# p2b-001.net
KiCad netlist of a schematic drawn in EAGLE
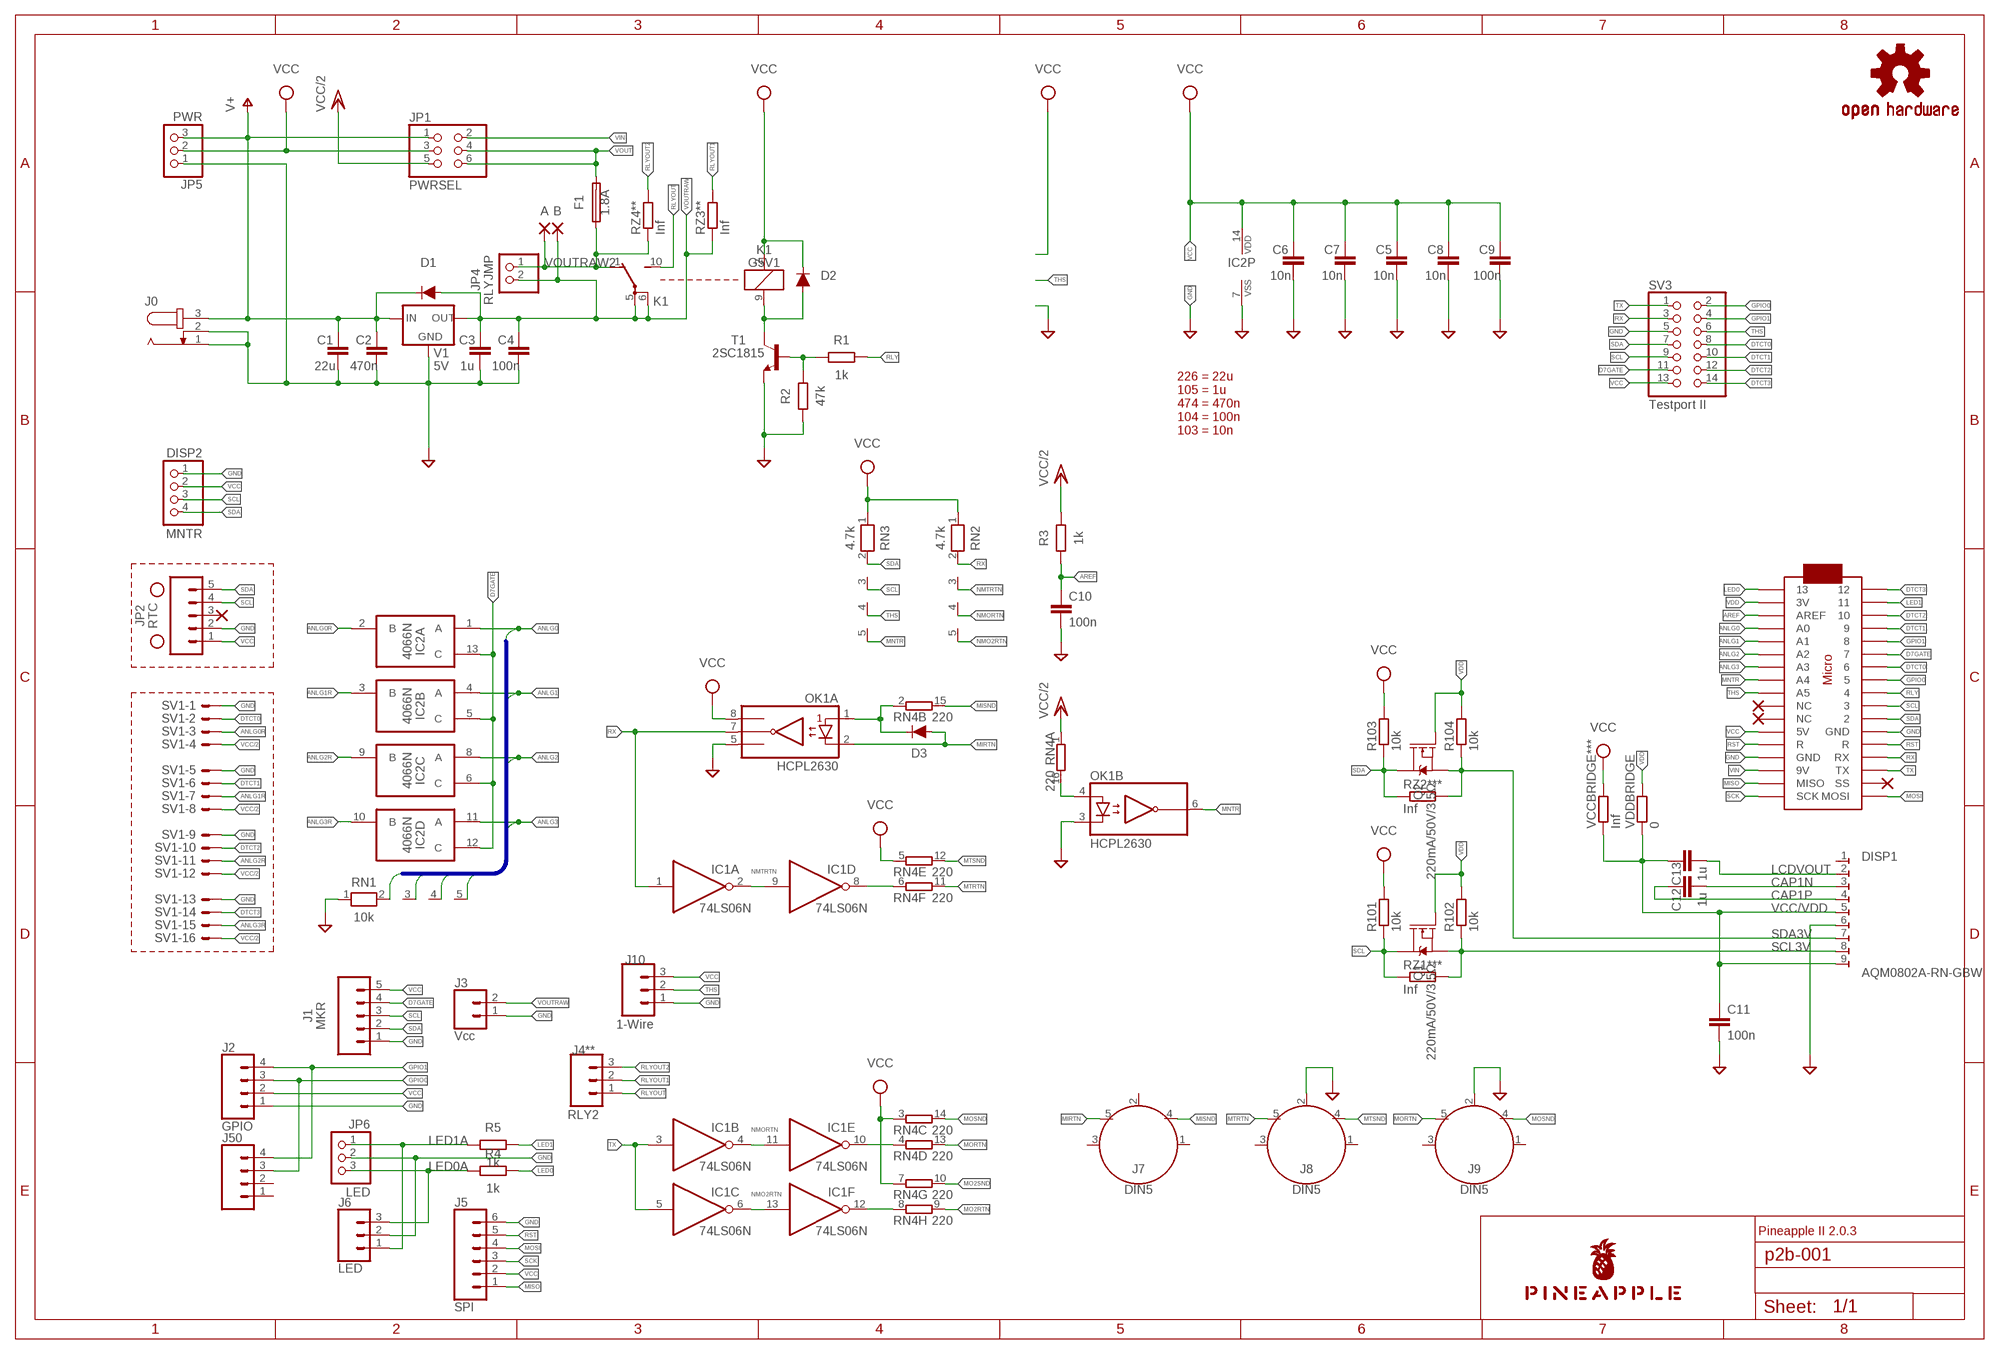
[diagram p0: schematic, sheet 1]

(export (version "E")
  (design (tool "Eeschema 10.0.6"))
  (components
    (comp (ref "A")
      (value "SMD2")
      (footprint "eagle-import:SMD1,27-2,54")
      (libsource (lib "eagle-import") (part "SMD2"))
    )
    (comp (ref "B")
      (value "SMD2")
      (footprint "eagle-import:SMD1,27-2,54")
      (libsource (lib "eagle-import") (part "SMD2"))
    )
    (comp (ref "C1")
      (value "22u")
      (footprint "eagle-import:C025-050X050")
      (libsource (lib "eagle-import") (part "C-EU025-050X050"))
    )
    (comp (ref "C2")
      (value "470n")
      (footprint "eagle-import:C050-024X044")
      (libsource (lib "eagle-import") (part "C-EU050-024X044"))
    )
    (comp (ref "C3")
      (value "1u")
      (footprint "eagle-import:C050-024X044")
      (libsource (lib "eagle-import") (part "C-EU050-024X044"))
    )
    (comp (ref "C4")
      (value "100n")
      (footprint "eagle-import:C025-024X044")
      (libsource (lib "eagle-import") (part "C-EU025-024X044"))
    )
    (comp (ref "C5")
      (value "10n")
      (footprint "eagle-import:C025-024X044")
      (libsource (lib "eagle-import") (part "resistor_348_C-EU025-024X044"))
    )
    (comp (ref "C6")
      (value "10n")
      (footprint "eagle-import:C025-024X044")
      (libsource (lib "eagle-import") (part "resistor_348_C-EU025-024X044"))
    )
    (comp (ref "C7")
      (value "10n")
      (footprint "eagle-import:C025-024X044")
      (libsource (lib "eagle-import") (part "resistor_348_C-EU025-024X044"))
    )
    (comp (ref "C8")
      (value "10n")
      (footprint "eagle-import:C025-024X044")
      (libsource (lib "eagle-import") (part "resistor_348_C-EU025-024X044"))
    )
    (comp (ref "C9")
      (value "100n")
      (footprint "eagle-import:C025-024X044")
      (libsource (lib "eagle-import") (part "resistor_348_C-EU025-024X044"))
    )
    (comp (ref "C10")
      (value "100n")
      (footprint "eagle-import:C025-024X044")
      (libsource (lib "eagle-import") (part "C-EU025-024X044"))
    )
    (comp (ref "C11")
      (value "100n")
      (footprint "eagle-import:C025-024X044")
      (libsource (lib "eagle-import") (part "C-EU025-024X044"))
    )
    (comp (ref "C12")
      (value "1u")
      (footprint "eagle-import:C050-024X044")
      (libsource (lib "eagle-import") (part "C-EU050-024X044"))
    )
    (comp (ref "C13")
      (value "1u")
      (footprint "eagle-import:C050-024X044")
      (libsource (lib "eagle-import") (part "C-EU050-024X044"))
    )
    (comp (ref "D1")
      (value "DIODE-1N4148")
      (footprint "eagle-import:DIODE-1N4148")
      (libsource (lib "eagle-import") (part "DIODE-1N4148"))
    )
    (comp (ref "D2")
      (value "DIODE-1N4148")
      (footprint "eagle-import:DIODE-1N4148")
      (libsource (lib "eagle-import") (part "DIODE-1N4148"))
    )
    (comp (ref "D3")
      (value "DIODE-1N4148")
      (footprint "eagle-import:DIODE-1N4148")
      (libsource (lib "eagle-import") (part "DIODE-1N4148"))
    )
    (comp (ref "DISP1")
      (value "AQM0802A-RN-GBW")
      (footprint "eagle-import:AQM0802A-RN-GBW-FOOTPRINT")
      (libsource (lib "eagle-import") (part "AQM0802A-RN-GBW"))
    )
    (comp (ref "DISP2")
      (value "MNTR")
      (footprint "eagle-import:1X04")
      (libsource (lib "eagle-import") (part "PINHD-1X4"))
    )
    (comp (ref "F1")
      (value "1.8A")
      (footprint "eagle-import:TE5")
      (libsource (lib "eagle-import") (part "TE5"))
    )
    (comp (ref "H1")
      (value "STAND-OFF")
      (footprint "eagle-import:STAND-OFF")
      (libsource (lib "eagle-import") (part "STAND-OFF"))
    )
    (comp (ref "H2")
      (value "STAND-OFF")
      (footprint "eagle-import:STAND-OFF")
      (libsource (lib "eagle-import") (part "STAND-OFF"))
    )
    (comp (ref "IC1")
      (value "74LS06N")
      (footprint "eagle-import:DIL14")
      (libsource (lib "eagle-import") (part "7406NLS"))
    )
    (comp (ref "IC2")
      (value "4066N")
      (footprint "eagle-import:DIL14")
      (libsource (lib "eagle-import") (part "4066N"))
    )
    (comp (ref "J0")
      (value "JACK-PLUG0")
      (footprint "eagle-import:SPC4077")
      (libsource (lib "eagle-import") (part "JACK-PLUG0"))
    )
    (comp (ref "J1")
      (value "MKR")
      (footprint "eagle-import:JST-5-PTH")
      (libsource (lib "eagle-import") (part "CONN_05JST"))
    )
    (comp (ref "J2")
      (value "GPIO")
      (footprint "eagle-import:JST-4-PTH")
      (libsource (lib "eagle-import") (part "CONN_04JST-PTH"))
    )
    (comp (ref "J3")
      (value "Vcc")
      (footprint "eagle-import:JST-2-PTH")
      (libsource (lib "eagle-import") (part "CONN_02JST-PTH-2"))
    )
    (comp (ref "J4**")
      (value "RLY2")
      (footprint "eagle-import:JST-3-PTH-NS")
      (libsource (lib "eagle-import") (part "CONN_03JST-PTH-NS"))
    )
    (comp (ref "J5")
      (value "SPI")
      (footprint "eagle-import:1X06_1.27MM")
      (libsource (lib "eagle-import") (part "CONN_061.27MM"))
    )
    (comp (ref "J6")
      (value "LED")
      (footprint "eagle-import:JST-3-PTH-VERT")
      (libsource (lib "eagle-import") (part "CONN_03JST-PTH-VERT"))
    )
    (comp (ref "J7")
      (value "DIN5")
      (footprint "eagle-import:DIN5-RA-PTH")
      (libsource (lib "eagle-import") (part "DIN5"))
    )
    (comp (ref "J8")
      (value "DIN5")
      (footprint "eagle-import:DIN5-RA-PTH")
      (libsource (lib "eagle-import") (part "DIN5"))
    )
    (comp (ref "J9")
      (value "DIN5")
      (footprint "eagle-import:DIN5-RA-PTH")
      (libsource (lib "eagle-import") (part "DIN5"))
    )
    (comp (ref "J10")
      (value "1-Wire")
      (footprint "eagle-import:JST-3-PTH-VERT")
      (libsource (lib "eagle-import") (part "CONN_03JST-PTH-VERT"))
    )
    (comp (ref "J50")
      (value "CONN_041.27MM")
      (footprint "eagle-import:1X04_1.27MM")
      (libsource (lib "eagle-import") (part "CONN_041.27MM"))
    )
    (comp (ref "JP1")
      (value "PWRSEL")
      (footprint "eagle-import:2X03")
      (libsource (lib "eagle-import") (part "PINHD-2X3"))
    )
    (comp (ref "JP2")
      (value "RTC")
      (footprint "eagle-import:1X05")
      (libsource (lib "eagle-import") (part "CONN_05"))
    )
    (comp (ref "JP4")
      (value "RLYJMP")
      (footprint "eagle-import:1X02")
      (libsource (lib "eagle-import") (part "PINHD-1X2"))
    )
    (comp (ref "JP5")
      (value "PWR")
      (footprint "eagle-import:1X03")
      (libsource (lib "eagle-import") (part "PINHD-1X3"))
    )
    (comp (ref "JP6")
      (value "LED")
      (footprint "eagle-import:1X03")
      (libsource (lib "eagle-import") (part "PINHD-1X3"))
    )
    (comp (ref "K1")
      (value "G5V1")
      (footprint "eagle-import:G5V1")
      (fields (field (name "MPN") "G5V-1-DC24"))
      (libsource (lib "eagle-import") (part "G5V1"))
    )
    (comp (ref "LOGO1")
      (value "OSHW-LOGOS-COPPER")
      (footprint "eagle-import:OSHW-LOGO-S_COPPER")
      (libsource (lib "eagle-import") (part "OSHW-LOGOS-COPPER"))
    )
    (comp (ref "MC1")
      (value "ARDUINOMICRO")
      (footprint "eagle-import:ARDUINOMICRO")
      (libsource (lib "eagle-import") (part "ARDUINOMICRO"))
    )
    (comp (ref "OK1")
      (value "HCPL2630")
      (footprint "eagle-import:DIL08")
      (fields (field (name "MF") "AGILENT TECHNOLOGIES") (field (name "MPN") "HCPL-2630-000E"))
      (libsource (lib "eagle-import") (part "HCPL2630"))
    )
    (comp (ref "Q1")
      (value "220mA/50V/3.5Ω")
      (footprint "eagle-import:SOT23-3")
      (libsource (lib "eagle-import") (part "MOSFET-NCH-BSS138"))
    )
    (comp (ref "Q2")
      (value "220mA/50V/3.5Ω")
      (footprint "eagle-import:SOT23-3")
      (libsource (lib "eagle-import") (part "MOSFET-NCH-BSS138"))
    )
    (comp (ref "R1")
      (value "1k")
      (footprint "eagle-import:0204_5")
      (libsource (lib "eagle-import") (part "resistor_348_R-EU_0204/5"))
    )
    (comp (ref "R2")
      (value "47k")
      (footprint "eagle-import:0204_5")
      (libsource (lib "eagle-import") (part "resistor_348_R-EU_0204/5"))
    )
    (comp (ref "R3")
      (value "1k")
      (footprint "eagle-import:0204_5")
      (libsource (lib "eagle-import") (part "resistor_348_R-EU_0204/5"))
    )
    (comp (ref "R4")
      (value "1k")
      (footprint "eagle-import:0204_5")
      (libsource (lib "eagle-import") (part "resistor_348_R-EU_0204/5"))
    )
    (comp (ref "R5")
      (value "1k")
      (footprint "eagle-import:0204_5")
      (libsource (lib "eagle-import") (part "resistor_348_R-EU_0204/5"))
    )
    (comp (ref "R101")
      (value "10k")
      (footprint "eagle-import:M2012")
      (libsource (lib "eagle-import") (part "R-EU_M2012"))
    )
    (comp (ref "R102")
      (value "10k")
      (footprint "eagle-import:M2012")
      (libsource (lib "eagle-import") (part "R-EU_M2012"))
    )
    (comp (ref "R103")
      (value "10k")
      (footprint "eagle-import:M2012")
      (libsource (lib "eagle-import") (part "R-EU_M2012"))
    )
    (comp (ref "R104")
      (value "10k")
      (footprint "eagle-import:M2012")
      (libsource (lib "eagle-import") (part "R-EU_M2012"))
    )
    (comp (ref "RN1")
      (value "10k")
      (footprint "eagle-import:RN-5")
      (libsource (lib "eagle-import") (part "RN04"))
    )
    (comp (ref "RN2")
      (value "4.7k")
      (footprint "eagle-import:RN-5")
      (libsource (lib "eagle-import") (part "RN04"))
    )
    (comp (ref "RN3")
      (value "4.7k")
      (footprint "eagle-import:RN-5")
      (libsource (lib "eagle-import") (part "RN04"))
    )
    (comp (ref "RN4")
      (value "220")
      (footprint "eagle-import:DIL16")
      (libsource (lib "eagle-import") (part "8R-N"))
    )
    (comp (ref "RZ1***")
      (value "Inf")
      (footprint "eagle-import:M2012")
      (libsource (lib "eagle-import") (part "R-EU_M2012"))
    )
    (comp (ref "RZ2***")
      (value "Inf")
      (footprint "eagle-import:M2012")
      (libsource (lib "eagle-import") (part "R-EU_M2012"))
    )
    (comp (ref "RZ3**")
      (value "Inf")
      (footprint "eagle-import:M2012")
      (libsource (lib "eagle-import") (part "R-EU_M2012"))
    )
    (comp (ref "RZ4**")
      (value "Inf")
      (footprint "eagle-import:M2012")
      (libsource (lib "eagle-import") (part "R-EU_M2012"))
    )
    (comp (ref "SV1")
      (value "ML16LE")
      (footprint "eagle-import:ML16L")
      (libsource (lib "eagle-import") (part "ML16LE"))
    )
    (comp (ref "SV3")
      (value "Testport II")
      (footprint "eagle-import:2X07")
      (libsource (lib "eagle-import") (part "PINHD-2X7"))
    )
    (comp (ref "T1")
      (value "2SC1815")
      (footprint "eagle-import:TO92-ECB")
      (libsource (lib "eagle-import") (part "2SC1815"))
    )
    (comp (ref "U$1")
      (value "PINEAPPLE450_SILK")
      (footprint "eagle-import:PINEAPPLE450_SILK")
      (libsource (lib "eagle-import") (part "PINEAPPLE450_SILK"))
    )
    (comp (ref "V1")
      (value "5V")
      (footprint "eagle-import:78XXL")
      (libsource (lib "eagle-import") (part "78XXL"))
    )
    (comp (ref "VCCBRIDGE***")
      (value "Inf")
      (footprint "eagle-import:M2012")
      (libsource (lib "eagle-import") (part "R-EU_M2012"))
    )
    (comp (ref "VDDBRIDGE")
      (value "0")
      (footprint "eagle-import:M2012")
      (libsource (lib "eagle-import") (part "R-EU_M2012"))
    )
  )
  (nets
    (net (code "1") (name "/CAP1N") (class "Default")
      (node (ref "C12") (pin "2") (pinfunction "2_2") (pintype "passive"))
      (node (ref "DISP1") (pin "3") (pinfunction "3_3") (pintype "passive"))
    )
    (net (code "2") (name "/CAP1P") (class "Default")
      (node (ref "C12") (pin "1") (pinfunction "1_1") (pintype "passive"))
      (node (ref "DISP1") (pin "4") (pinfunction "4_4") (pintype "passive"))
    )
    (net (code "3") (name "/LCDVOUT") (class "Default")
      (node (ref "C13") (pin "2") (pinfunction "2_2") (pintype "passive"))
      (node (ref "DISP1") (pin "2") (pinfunction "2_2") (pintype "passive"))
    )
    (net (code "4") (name "/LED0A") (class "Default")
      (node (ref "J6") (pin "3") (pinfunction "3_3") (pintype "passive"))
      (node (ref "JP6") (pin "3") (pinfunction "3_3") (pintype "passive"))
      (node (ref "R4") (pin "1") (pinfunction "1_1") (pintype "passive"))
    )
    (net (code "5") (name "/LED1A") (class "Default")
      (node (ref "J6") (pin "1") (pinfunction "1_1") (pintype "passive"))
      (node (ref "JP6") (pin "1") (pinfunction "1_1") (pintype "passive"))
      (node (ref "R5") (pin "1") (pinfunction "1_1") (pintype "passive"))
    )
    (net (code "6") (name "/SCL3V") (class "Default")
      (node (ref "DISP1") (pin "8") (pinfunction "8_8") (pintype "passive"))
      (node (ref "Q1") (pin "2") (pinfunction "S_2") (pintype "bidirectional"))
      (node (ref "R102") (pin "1") (pinfunction "1_1") (pintype "passive"))
      (node (ref "RZ1***") (pin "2") (pinfunction "2_2") (pintype "passive"))
    )
    (net (code "7") (name "/SDA3V") (class "Default")
      (node (ref "DISP1") (pin "7") (pinfunction "7_7") (pintype "passive"))
      (node (ref "Q2") (pin "2") (pinfunction "S_2") (pintype "bidirectional"))
      (node (ref "R104") (pin "1") (pinfunction "1_1") (pintype "passive"))
      (node (ref "RZ2***") (pin "2") (pinfunction "2_2") (pintype "passive"))
    )
    (net (code "8") (name "/VCC{slash}VDD") (class "Default")
      (node (ref "C11") (pin "1") (pinfunction "1_1") (pintype "passive"))
      (node (ref "C13") (pin "1") (pinfunction "1_1") (pintype "passive"))
      (node (ref "DISP1") (pin "5") (pinfunction "5_5") (pintype "passive"))
      (node (ref "DISP1") (pin "9") (pinfunction "9_9") (pintype "passive"))
      (node (ref "VCCBRIDGE***") (pin "1") (pinfunction "1_1") (pintype "passive"))
      (node (ref "VDDBRIDGE") (pin "1") (pinfunction "1_1") (pintype "passive"))
    )
    (net (code "9") (name "/VOUTRAW2") (class "Default")
      (node (ref "A") (pin "1") (pinfunction "P_1") (pintype "passive"))
      (node (ref "F1") (pin "1") (pinfunction "1_1") (pintype "passive"))
      (node (ref "JP4") (pin "1") (pinfunction "1_1") (pintype "passive"))
      (node (ref "K1") (pin "1") (pinfunction "O_1") (pintype "passive"))
      (node (ref "RZ4**") (pin "1") (pinfunction "1_1") (pintype "passive"))
    )
    (net (code "10") (name "ANLG0") (class "Default")
      (node (ref "IC2") (pin "1") (pinfunction "A_1") (pintype "tri_state"))
      (node (ref "MC1") (pin "P$31") (pinfunction "A0_P$31") (pintype "bidirectional"))
      (node (ref "RN1") (pin "2") (pinfunction "2_2") (pintype "passive"))
    )
    (net (code "11") (name "ANLG0R") (class "Default")
      (node (ref "IC2") (pin "2") (pinfunction "B_2") (pintype "tri_state"))
      (node (ref "SV1") (pin "3") (pinfunction "S_3") (pintype "passive"))
    )
    (net (code "12") (name "ANLG1") (class "Default")
      (node (ref "IC2") (pin "4") (pinfunction "A_4") (pintype "tri_state"))
      (node (ref "MC1") (pin "P$30") (pinfunction "A1_P$30") (pintype "bidirectional"))
      (node (ref "RN1") (pin "3") (pinfunction "3_3") (pintype "passive"))
    )
    (net (code "13") (name "ANLG1R") (class "Default")
      (node (ref "IC2") (pin "3") (pinfunction "B_3") (pintype "tri_state"))
      (node (ref "SV1") (pin "7") (pinfunction "S_7") (pintype "passive"))
    )
    (net (code "14") (name "ANLG2") (class "Default")
      (node (ref "IC2") (pin "8") (pinfunction "A_8") (pintype "tri_state"))
      (node (ref "MC1") (pin "P$29") (pinfunction "A2_P$29") (pintype "bidirectional"))
      (node (ref "RN1") (pin "4") (pinfunction "4_4") (pintype "passive"))
    )
    (net (code "15") (name "ANLG2R") (class "Default")
      (node (ref "IC2") (pin "9") (pinfunction "B_9") (pintype "tri_state"))
      (node (ref "SV1") (pin "11") (pinfunction "S_11") (pintype "passive"))
    )
    (net (code "16") (name "ANLG3") (class "Default")
      (node (ref "IC2") (pin "11") (pinfunction "A_11") (pintype "tri_state"))
      (node (ref "MC1") (pin "P$28") (pinfunction "A3_P$28") (pintype "bidirectional"))
      (node (ref "RN1") (pin "5") (pinfunction "5_5") (pintype "passive"))
    )
    (net (code "17") (name "ANLG3R") (class "Default")
      (node (ref "IC2") (pin "10") (pinfunction "B_10") (pintype "tri_state"))
      (node (ref "SV1") (pin "15") (pinfunction "S_15") (pintype "passive"))
    )
    (net (code "18") (name "AREF") (class "Default")
      (node (ref "C10") (pin "1") (pinfunction "1_1") (pintype "passive"))
      (node (ref "MC1") (pin "P$32") (pinfunction "AREF_P$32") (pintype "bidirectional"))
      (node (ref "R3") (pin "1") (pinfunction "1_1") (pintype "passive"))
    )
    (net (code "19") (name "D7GATE") (class "Default")
      (node (ref "IC2") (pin "12") (pinfunction "C_12") (pintype "input"))
      (node (ref "IC2") (pin "13") (pinfunction "C_13") (pintype "input"))
      (node (ref "IC2") (pin "5") (pinfunction "C_5") (pintype "input"))
      (node (ref "IC2") (pin "6") (pinfunction "C_6") (pintype "input"))
      (node (ref "J1") (pin "4") (pinfunction "4_4") (pintype "passive"))
      (node (ref "MC1") (pin "P$6") (pinfunction "7_P$6") (pintype "bidirectional"))
      (node (ref "SV3") (pin "11") (pinfunction "11_11") (pintype "passive"))
    )
    (net (code "20") (name "DTCT0") (class "Default")
      (node (ref "MC1") (pin "P$7") (pinfunction "6_P$7") (pintype "bidirectional"))
      (node (ref "SV1") (pin "2") (pinfunction "S_2") (pintype "passive"))
      (node (ref "SV3") (pin "8") (pinfunction "8_8") (pintype "passive"))
    )
    (net (code "21") (name "DTCT1") (class "Default")
      (node (ref "MC1") (pin "P$4") (pinfunction "9_P$4") (pintype "bidirectional"))
      (node (ref "SV1") (pin "6") (pinfunction "S_6") (pintype "passive"))
      (node (ref "SV3") (pin "10") (pinfunction "10_10") (pintype "passive"))
    )
    (net (code "22") (name "DTCT2") (class "Default")
      (node (ref "MC1") (pin "P$3") (pinfunction "10_P$3") (pintype "bidirectional"))
      (node (ref "SV1") (pin "10") (pinfunction "S_10") (pintype "passive"))
      (node (ref "SV3") (pin "12") (pinfunction "12_12") (pintype "passive"))
    )
    (net (code "23") (name "DTCT3") (class "Default")
      (node (ref "MC1") (pin "P$1") (pinfunction "12_P$1") (pintype "bidirectional"))
      (node (ref "SV1") (pin "14") (pinfunction "S_14") (pintype "passive"))
      (node (ref "SV3") (pin "14") (pinfunction "14_14") (pintype "passive"))
    )
    (net (code "24") (name "GND") (class "Default")
      (node (ref "C1") (pin "2") (pinfunction "2_2") (pintype "passive"))
      (node (ref "C10") (pin "2") (pinfunction "2_2") (pintype "passive"))
      (node (ref "C11") (pin "2") (pinfunction "2_2") (pintype "passive"))
      (node (ref "C2") (pin "2") (pinfunction "2_2") (pintype "passive"))
      (node (ref "C3") (pin "2") (pinfunction "2_2") (pintype "passive"))
      (node (ref "C4") (pin "2") (pinfunction "2_2") (pintype "passive"))
      (node (ref "C5") (pin "2") (pinfunction "2_2") (pintype "passive"))
      (node (ref "C6") (pin "2") (pinfunction "2_2") (pintype "passive"))
      (node (ref "C7") (pin "2") (pinfunction "2_2") (pintype "passive"))
      (node (ref "C8") (pin "2") (pinfunction "2_2") (pintype "passive"))
      (node (ref "C9") (pin "2") (pinfunction "2_2") (pintype "passive"))
      (node (ref "DISP1") (pin "6") (pinfunction "6_6") (pintype "passive"))
      (node (ref "DISP2") (pin "1") (pinfunction "1_1") (pintype "passive"))
      (node (ref "IC2") (pin "7") (pinfunction "VSS_7") (pintype "power_in"))
      (node (ref "J0") (pin "1") (pinfunction "1_1") (pintype "passive"))
      (node (ref "J0") (pin "2") (pinfunction "2_2") (pintype "passive"))
      (node (ref "J1") (pin "1") (pinfunction "1_1") (pintype "passive"))
      (node (ref "J10") (pin "1") (pinfunction "1_1") (pintype "passive"))
      (node (ref "J2") (pin "1") (pinfunction "1_1") (pintype "passive"))
      (node (ref "J3") (pin "1") (pinfunction "1_1") (pintype "passive"))
      (node (ref "J5") (pin "6") (pinfunction "6_6") (pintype "passive"))
      (node (ref "J6") (pin "2") (pinfunction "2_2") (pintype "passive"))
      (node (ref "J8") (pin "2") (pinfunction "2_2") (pintype "bidirectional"))
      (node (ref "J9") (pin "2") (pinfunction "2_2") (pintype "bidirectional"))
      (node (ref "JP2") (pin "2") (pinfunction "2_2") (pintype "passive"))
      (node (ref "JP5") (pin "1") (pinfunction "1_1") (pintype "passive"))
      (node (ref "JP6") (pin "2") (pinfunction "2_2") (pintype "passive"))
      (node (ref "MC1") (pin "P$12") (pinfunction "GND_P$12") (pintype "bidirectional"))
      (node (ref "MC1") (pin "P$21") (pinfunction "GND_P$21") (pintype "bidirectional"))
      (node (ref "OK1") (pin "3") (pinfunction "C2_3") (pintype "passive"))
      (node (ref "OK1") (pin "5") (pinfunction "GND_5") (pintype "passive"))
      (node (ref "R2") (pin "1") (pinfunction "1_1") (pintype "passive"))
      (node (ref "RN1") (pin "1") (pinfunction "1_1") (pintype "passive"))
      (node (ref "SV1") (pin "1") (pinfunction "S_1") (pintype "passive"))
      (node (ref "SV1") (pin "13") (pinfunction "S_13") (pintype "passive"))
      (node (ref "SV1") (pin "5") (pinfunction "S_5") (pintype "passive"))
      (node (ref "SV1") (pin "9") (pinfunction "S_9") (pintype "passive"))
      (node (ref "SV3") (pin "5") (pinfunction "5_5") (pintype "passive"))
      (node (ref "T1") (pin "E") (pinfunction "E_E") (pintype "passive"))
      (node (ref "V1") (pin "GND") (pinfunction "GND_GND") (pintype "input"))
    )
    (net (code "25") (name "GPIO0") (class "Default")
      (node (ref "J2") (pin "3") (pinfunction "3_3") (pintype "passive"))
      (node (ref "J50") (pin "3") (pinfunction "3_3") (pintype "passive"))
      (node (ref "MC1") (pin "P$8") (pinfunction "5_P$8") (pintype "bidirectional"))
      (node (ref "SV3") (pin "2") (pinfunction "2_2") (pintype "passive"))
    )
    (net (code "26") (name "GPIO1") (class "Default")
      (node (ref "J2") (pin "4") (pinfunction "4_4") (pintype "passive"))
      (node (ref "J50") (pin "4") (pinfunction "4_4") (pintype "passive"))
      (node (ref "MC1") (pin "P$5") (pinfunction "8_P$5") (pintype "bidirectional"))
      (node (ref "SV3") (pin "4") (pinfunction "4_4") (pintype "passive"))
    )
    (net (code "27") (name "LED0") (class "Default")
      (node (ref "MC1") (pin "P$34") (pinfunction "13_P$34") (pintype "bidirectional"))
      (node (ref "R4") (pin "2") (pinfunction "2_2") (pintype "passive"))
    )
    (net (code "28") (name "LED1") (class "Default")
      (node (ref "MC1") (pin "P$2") (pinfunction "11_P$2") (pintype "bidirectional"))
      (node (ref "R5") (pin "2") (pinfunction "2_2") (pintype "passive"))
    )
    (net (code "29") (name "MIRTN") (class "Default")
      (node (ref "D3") (pin "A") (pinfunction "A_A") (pintype "passive"))
      (node (ref "J7") (pin "5") (pinfunction "5_5") (pintype "bidirectional"))
      (node (ref "OK1") (pin "2") (pinfunction "C1_2") (pintype "passive"))
    )
    (net (code "30") (name "MISND") (class "Default")
      (node (ref "J7") (pin "4") (pinfunction "4_4") (pintype "bidirectional"))
      (node (ref "RN4") (pin "15") (pinfunction "2_15") (pintype "passive"))
    )
    (net (code "31") (name "MISO") (class "Default")
      (node (ref "J5") (pin "1") (pinfunction "1_1") (pintype "passive"))
      (node (ref "MC1") (pin "P$19") (pinfunction "MISO_P$19") (pintype "bidirectional"))
    )
    (net (code "32") (name "MNTR") (class "Default")
      (node (ref "MC1") (pin "P$27") (pinfunction "A4_P$27") (pintype "bidirectional"))
      (node (ref "OK1") (pin "6") (pinfunction "VO2_6") (pintype "passive"))
      (node (ref "RN3") (pin "5") (pinfunction "5_5") (pintype "passive"))
    )
    (net (code "33") (name "MO2RTN") (class "Default")
      (node (ref "RN4") (pin "9") (pinfunction "2_9") (pintype "passive"))
    )
    (net (code "34") (name "MO2SND") (class "Default")
      (node (ref "RN4") (pin "10") (pinfunction "2_10") (pintype "passive"))
    )
    (net (code "35") (name "MORTN") (class "Default")
      (node (ref "J9") (pin "5") (pinfunction "5_5") (pintype "bidirectional"))
      (node (ref "RN4") (pin "13") (pinfunction "2_13") (pintype "passive"))
    )
    (net (code "36") (name "MOSI") (class "Default")
      (node (ref "J5") (pin "4") (pinfunction "4_4") (pintype "passive"))
      (node (ref "MC1") (pin "P$17") (pinfunction "MOSI_P$17") (pintype "bidirectional"))
    )
    (net (code "37") (name "MOSND") (class "Default")
      (node (ref "J9") (pin "4") (pinfunction "4_4") (pintype "bidirectional"))
      (node (ref "RN4") (pin "14") (pinfunction "2_14") (pintype "passive"))
    )
    (net (code "38") (name "MTRTN") (class "Default")
      (node (ref "J8") (pin "5") (pinfunction "5_5") (pintype "bidirectional"))
      (node (ref "RN4") (pin "11") (pinfunction "2_11") (pintype "passive"))
    )
    (net (code "39") (name "MTSND") (class "Default")
      (node (ref "J8") (pin "4") (pinfunction "4_4") (pintype "bidirectional"))
      (node (ref "RN4") (pin "12") (pinfunction "2_12") (pintype "passive"))
    )
    (net (code "40") (name "NMO2RTN") (class "Default")
      (node (ref "IC1") (pin "13") (pinfunction "I_13") (pintype "input"))
      (node (ref "IC1") (pin "6") (pinfunction "O_6") (pintype "open_collector"))
      (node (ref "RN2") (pin "5") (pinfunction "5_5") (pintype "passive"))
    )
    (net (code "41") (name "NMORTN") (class "Default")
      (node (ref "IC1") (pin "11") (pinfunction "I_11") (pintype "input"))
      (node (ref "IC1") (pin "4") (pinfunction "O_4") (pintype "open_collector"))
      (node (ref "RN2") (pin "4") (pinfunction "4_4") (pintype "passive"))
    )
    (net (code "42") (name "NMTRTN") (class "Default")
      (node (ref "IC1") (pin "2") (pinfunction "O_2") (pintype "open_collector"))
      (node (ref "IC1") (pin "9") (pinfunction "I_9") (pintype "input"))
      (node (ref "RN2") (pin "3") (pinfunction "3_3") (pintype "passive"))
    )
    (net (code "43") (name "Net-(IC1D-O)") (class "Default")
      (node (ref "IC1") (pin "8") (pinfunction "O_8") (pintype "open_collector"))
      (node (ref "RN4") (pin "6") (pinfunction "1_6") (pintype "passive"))
    )
    (net (code "44") (name "Net-(IC1E-O)") (class "Default")
      (node (ref "IC1") (pin "10") (pinfunction "O_10") (pintype "open_collector"))
      (node (ref "RN4") (pin "4") (pinfunction "1_4") (pintype "passive"))
    )
    (net (code "45") (name "Net-(IC1F-O)") (class "Default")
      (node (ref "IC1") (pin "12") (pinfunction "O_12") (pintype "open_collector"))
      (node (ref "RN4") (pin "8") (pinfunction "1_8") (pintype "passive"))
    )
    (net (code "46") (name "Net-(K1A-2)") (class "Default")
      (node (ref "D2") (pin "A") (pinfunction "A_A") (pintype "passive"))
      (node (ref "K1") (pin "9") (pinfunction "2_9") (pintype "passive"))
      (node (ref "T1") (pin "C") (pinfunction "C_C") (pintype "passive"))
    )
    (net (code "47") (name "Net-(OK1A-A1)") (class "Default")
      (node (ref "D3") (pin "C") (pinfunction "C_C") (pintype "passive"))
      (node (ref "OK1") (pin "1") (pinfunction "A1_1") (pintype "passive"))
      (node (ref "RN4") (pin "2") (pinfunction "1_2") (pintype "passive"))
    )
    (net (code "48") (name "Net-(OK1B-A2)") (class "Default")
      (node (ref "OK1") (pin "4") (pinfunction "A2_4") (pintype "passive"))
      (node (ref "RN4") (pin "16") (pinfunction "2_16") (pintype "passive"))
    )
    (net (code "49") (name "Net-(R1-Pad1)") (class "Default")
      (node (ref "R1") (pin "1") (pinfunction "1_1") (pintype "passive"))
      (node (ref "R2") (pin "2") (pinfunction "2_2") (pintype "passive"))
      (node (ref "T1") (pin "B") (pinfunction "B_B") (pintype "passive"))
    )
    (net (code "50") (name "RLY") (class "Default")
      (node (ref "MC1") (pin "P$9") (pinfunction "4_P$9") (pintype "bidirectional"))
      (node (ref "R1") (pin "2") (pinfunction "2_2") (pintype "passive"))
    )
    (net (code "51") (name "RLYOUT") (class "Default")
      (node (ref "J4**") (pin "1") (pinfunction "1_1") (pintype "passive"))
      (node (ref "K1") (pin "10") (pinfunction "S_10") (pintype "passive"))
    )
    (net (code "52") (name "RLYOUT1") (class "Default")
      (node (ref "J4**") (pin "2") (pinfunction "2_2") (pintype "passive"))
      (node (ref "RZ3**") (pin "2") (pinfunction "2_2") (pintype "passive"))
    )
    (net (code "53") (name "RLYOUT2") (class "Default")
      (node (ref "J4**") (pin "3") (pinfunction "3_3") (pintype "passive"))
      (node (ref "RZ4**") (pin "2") (pinfunction "2_2") (pintype "passive"))
    )
    (net (code "54") (name "RST") (class "Default")
      (node (ref "J5") (pin "5") (pinfunction "5_5") (pintype "passive"))
      (node (ref "MC1") (pin "P$13") (pinfunction "R_P$13") (pintype "bidirectional"))
      (node (ref "MC1") (pin "P$22") (pinfunction "R_P$22") (pintype "bidirectional"))
    )
    (net (code "55") (name "RX") (class "Default")
      (node (ref "IC1") (pin "1") (pinfunction "I_1") (pintype "input"))
      (node (ref "MC1") (pin "P$14") (pinfunction "RX_P$14") (pintype "bidirectional"))
      (node (ref "OK1") (pin "7") (pinfunction "VO1_7") (pintype "passive"))
      (node (ref "RN2") (pin "2") (pinfunction "2_2") (pintype "passive"))
      (node (ref "SV3") (pin "3") (pinfunction "3_3") (pintype "passive"))
    )
    (net (code "56") (name "SCK") (class "Default")
      (node (ref "J5") (pin "3") (pinfunction "3_3") (pintype "passive"))
      (node (ref "MC1") (pin "P$18") (pinfunction "SCK_P$18") (pintype "bidirectional"))
    )
    (net (code "57") (name "SCL") (class "Default")
      (node (ref "DISP2") (pin "3") (pinfunction "3_3") (pintype "passive"))
      (node (ref "J1") (pin "3") (pinfunction "3_3") (pintype "passive"))
      (node (ref "JP2") (pin "4") (pinfunction "4_4") (pintype "passive"))
      (node (ref "MC1") (pin "P$10") (pinfunction "3_P$10") (pintype "bidirectional"))
      (node (ref "Q1") (pin "3") (pinfunction "D_3") (pintype "bidirectional"))
      (node (ref "R101") (pin "1") (pinfunction "1_1") (pintype "passive"))
      (node (ref "RN3") (pin "3") (pinfunction "3_3") (pintype "passive"))
      (node (ref "RZ1***") (pin "1") (pinfunction "1_1") (pintype "passive"))
      (node (ref "SV3") (pin "9") (pinfunction "9_9") (pintype "passive"))
    )
    (net (code "58") (name "SDA") (class "Default")
      (node (ref "DISP2") (pin "4") (pinfunction "4_4") (pintype "passive"))
      (node (ref "J1") (pin "2") (pinfunction "2_2") (pintype "passive"))
      (node (ref "JP2") (pin "5") (pinfunction "5_5") (pintype "passive"))
      (node (ref "MC1") (pin "P$11") (pinfunction "2_P$11") (pintype "bidirectional"))
      (node (ref "Q2") (pin "3") (pinfunction "D_3") (pintype "bidirectional"))
      (node (ref "R103") (pin "1") (pinfunction "1_1") (pintype "passive"))
      (node (ref "RN3") (pin "2") (pinfunction "2_2") (pintype "passive"))
      (node (ref "RZ2***") (pin "1") (pinfunction "1_1") (pintype "passive"))
      (node (ref "SV3") (pin "7") (pinfunction "7_7") (pintype "passive"))
    )
    (net (code "59") (name "THS") (class "Default")
      (node (ref "J10") (pin "2") (pinfunction "2_2") (pintype "passive"))
      (node (ref "MC1") (pin "P$26") (pinfunction "A5_P$26") (pintype "bidirectional"))
      (node (ref "RN3") (pin "4") (pinfunction "4_4") (pintype "passive"))
      (node (ref "SV3") (pin "6") (pinfunction "6_6") (pintype "passive"))
    )
    (net (code "60") (name "TX") (class "Default")
      (node (ref "IC1") (pin "3") (pinfunction "I_3") (pintype "input"))
      (node (ref "IC1") (pin "5") (pinfunction "I_5") (pintype "input"))
      (node (ref "MC1") (pin "P$15") (pinfunction "TX_P$15") (pintype "bidirectional"))
      (node (ref "SV3") (pin "1") (pinfunction "1_1") (pintype "passive"))
    )
    (net (code "61") (name "V+") (class "Default")
      (node (ref "C1") (pin "1") (pinfunction "1_1") (pintype "passive"))
      (node (ref "C2") (pin "1") (pinfunction "1_1") (pintype "passive"))
      (node (ref "D1") (pin "C") (pinfunction "C_C") (pintype "passive"))
      (node (ref "J0") (pin "3") (pinfunction "3_3") (pintype "passive"))
      (node (ref "JP1") (pin "1") (pinfunction "1_1") (pintype "passive"))
      (node (ref "JP5") (pin "3") (pinfunction "3_3") (pintype "passive"))
      (node (ref "V1") (pin "IN") (pinfunction "IN_IN") (pintype "input"))
    )
    (net (code "62") (name "VCC") (class "Default")
      (node (ref "C5") (pin "1") (pinfunction "1_1") (pintype "passive"))
      (node (ref "C6") (pin "1") (pinfunction "1_1") (pintype "passive"))
      (node (ref "C7") (pin "1") (pinfunction "1_1") (pintype "passive"))
      (node (ref "C8") (pin "1") (pinfunction "1_1") (pintype "passive"))
      (node (ref "C9") (pin "1") (pinfunction "1_1") (pintype "passive"))
      (node (ref "D2") (pin "C") (pinfunction "C_C") (pintype "passive"))
      (node (ref "DISP2") (pin "2") (pinfunction "2_2") (pintype "passive"))
      (node (ref "IC2") (pin "14") (pinfunction "VDD_14") (pintype "power_in"))
      (node (ref "J1") (pin "5") (pinfunction "5_5") (pintype "passive"))
      (node (ref "J10") (pin "3") (pinfunction "3_3") (pintype "passive"))
      (node (ref "J2") (pin "2") (pinfunction "2_2") (pintype "passive"))
      (node (ref "J5") (pin "2") (pinfunction "2_2") (pintype "passive"))
      (node (ref "JP1") (pin "3") (pinfunction "3_3") (pintype "passive"))
      (node (ref "JP2") (pin "1") (pinfunction "1_1") (pintype "passive"))
      (node (ref "JP5") (pin "2") (pinfunction "2_2") (pintype "passive"))
      (node (ref "K1") (pin "2") (pinfunction "1_2") (pintype "passive"))
      (node (ref "MC1") (pin "P$23") (pinfunction "5V_P$23") (pintype "bidirectional"))
      (node (ref "OK1") (pin "8") (pinfunction "VCC_8") (pintype "passive"))
      (node (ref "R101") (pin "2") (pinfunction "2_2") (pintype "passive"))
      (node (ref "R103") (pin "2") (pinfunction "2_2") (pintype "passive"))
      (node (ref "RN2") (pin "1") (pinfunction "1_1") (pintype "passive"))
      (node (ref "RN3") (pin "1") (pinfunction "1_1") (pintype "passive"))
      (node (ref "RN4") (pin "3") (pinfunction "1_3") (pintype "passive"))
      (node (ref "RN4") (pin "5") (pinfunction "1_5") (pintype "passive"))
      (node (ref "RN4") (pin "7") (pinfunction "1_7") (pintype "passive"))
      (node (ref "SV3") (pin "13") (pinfunction "13_13") (pintype "passive"))
      (node (ref "VCCBRIDGE***") (pin "2") (pinfunction "2_2") (pintype "passive"))
    )
    (net (code "63") (name "VCC{slash}2") (class "Default")
      (node (ref "JP1") (pin "5") (pinfunction "5_5") (pintype "passive"))
      (node (ref "R3") (pin "2") (pinfunction "2_2") (pintype "passive"))
      (node (ref "RN4") (pin "1") (pinfunction "1_1") (pintype "passive"))
      (node (ref "SV1") (pin "12") (pinfunction "S_12") (pintype "passive"))
      (node (ref "SV1") (pin "16") (pinfunction "S_16") (pintype "passive"))
      (node (ref "SV1") (pin "4") (pinfunction "S_4") (pintype "passive"))
      (node (ref "SV1") (pin "8") (pinfunction "S_8") (pintype "passive"))
    )
    (net (code "64") (name "VDD") (class "Default")
      (node (ref "MC1") (pin "P$33") (pinfunction "3V_P$33") (pintype "bidirectional"))
      (node (ref "Q1") (pin "1") (pinfunction "G_1") (pintype "bidirectional"))
      (node (ref "Q2") (pin "1") (pinfunction "G_1") (pintype "bidirectional"))
      (node (ref "R102") (pin "2") (pinfunction "2_2") (pintype "passive"))
      (node (ref "R104") (pin "2") (pinfunction "2_2") (pintype "passive"))
      (node (ref "VDDBRIDGE") (pin "2") (pinfunction "2_2") (pintype "passive"))
    )
    (net (code "65") (name "VIN") (class "Default")
      (node (ref "JP1") (pin "2") (pinfunction "2_2") (pintype "passive"))
      (node (ref "MC1") (pin "P$20") (pinfunction "9V_P$20") (pintype "bidirectional"))
    )
    (net (code "66") (name "VOUT") (class "Default")
      (node (ref "F1") (pin "2") (pinfunction "2_2") (pintype "passive"))
      (node (ref "JP1") (pin "4") (pinfunction "4_4") (pintype "passive"))
      (node (ref "JP1") (pin "6") (pinfunction "6_6") (pintype "passive"))
    )
    (net (code "67") (name "VOUTRAW") (class "Default")
      (node (ref "B") (pin "1") (pinfunction "P_1") (pintype "passive"))
      (node (ref "C3") (pin "1") (pinfunction "1_1") (pintype "passive"))
      (node (ref "C4") (pin "1") (pinfunction "1_1") (pintype "passive"))
      (node (ref "D1") (pin "A") (pinfunction "A_A") (pintype "passive"))
      (node (ref "J3") (pin "2") (pinfunction "2_2") (pintype "passive"))
      (node (ref "JP4") (pin "2") (pinfunction "2_2") (pintype "passive"))
      (node (ref "K1") (pin "5") (pinfunction "P_5") (pintype "passive"))
      (node (ref "K1") (pin "6") (pinfunction "P_6") (pintype "passive"))
      (node (ref "RZ3**") (pin "1") (pinfunction "1_1") (pintype "passive"))
      (node (ref "V1") (pin "OUT") (pinfunction "OUT_OUT") (pintype "passive"))
    )
    (net (code "68") (name "unconnected-(DISP1-Pad1)") (class "Default")
      (node (ref "DISP1") (pin "1") (pinfunction "1_1") (pintype "passive"))
    )
    (net (code "69") (name "unconnected-(J7-Pad1)") (class "Default")
      (node (ref "J7") (pin "1") (pinfunction "1_1") (pintype "bidirectional"))
    )
    (net (code "70") (name "unconnected-(J7-Pad2)") (class "Default")
      (node (ref "J7") (pin "2") (pinfunction "2_2") (pintype "bidirectional"))
    )
    (net (code "71") (name "unconnected-(J7-Pad3)") (class "Default")
      (node (ref "J7") (pin "3") (pinfunction "3_3") (pintype "bidirectional"))
    )
    (net (code "72") (name "unconnected-(J8-Pad1)") (class "Default")
      (node (ref "J8") (pin "1") (pinfunction "1_1") (pintype "bidirectional"))
    )
    (net (code "73") (name "unconnected-(J8-Pad3)") (class "Default")
      (node (ref "J8") (pin "3") (pinfunction "3_3") (pintype "bidirectional"))
    )
    (net (code "74") (name "unconnected-(J9-Pad1)") (class "Default")
      (node (ref "J9") (pin "1") (pinfunction "1_1") (pintype "bidirectional"))
    )
    (net (code "75") (name "unconnected-(J9-Pad3)") (class "Default")
      (node (ref "J9") (pin "3") (pinfunction "3_3") (pintype "bidirectional"))
    )
    (net (code "76") (name "unconnected-(J50-Pad1)") (class "Default")
      (node (ref "J50") (pin "1") (pinfunction "1_1") (pintype "passive"))
    )
    (net (code "77") (name "unconnected-(J50-Pad2)") (class "Default")
      (node (ref "J50") (pin "2") (pinfunction "2_2") (pintype "passive"))
    )
    (net (code "78") (name "unconnected-(JP2-Pad3)") (class "Default")
      (node (ref "JP2") (pin "3") (pinfunction "3_3") (pintype "passive"))
    )
    (net (code "79") (name "unconnected-(MC1-NC-PadP$24)") (class "Default")
      (node (ref "MC1") (pin "P$24") (pinfunction "NC_P$24") (pintype "bidirectional"))
    )
    (net (code "80") (name "unconnected-(MC1-NC-PadP$25)") (class "Default")
      (node (ref "MC1") (pin "P$25") (pinfunction "NC_P$25") (pintype "bidirectional"))
    )
    (net (code "81") (name "unconnected-(MC1-SS-PadP$16)") (class "Default")
      (node (ref "MC1") (pin "P$16") (pinfunction "SS_P$16") (pintype "bidirectional"))
    )
  )
)
